# 04_Analog_Part.net
KiCad netlist of a schematic drawn in Altium Designer
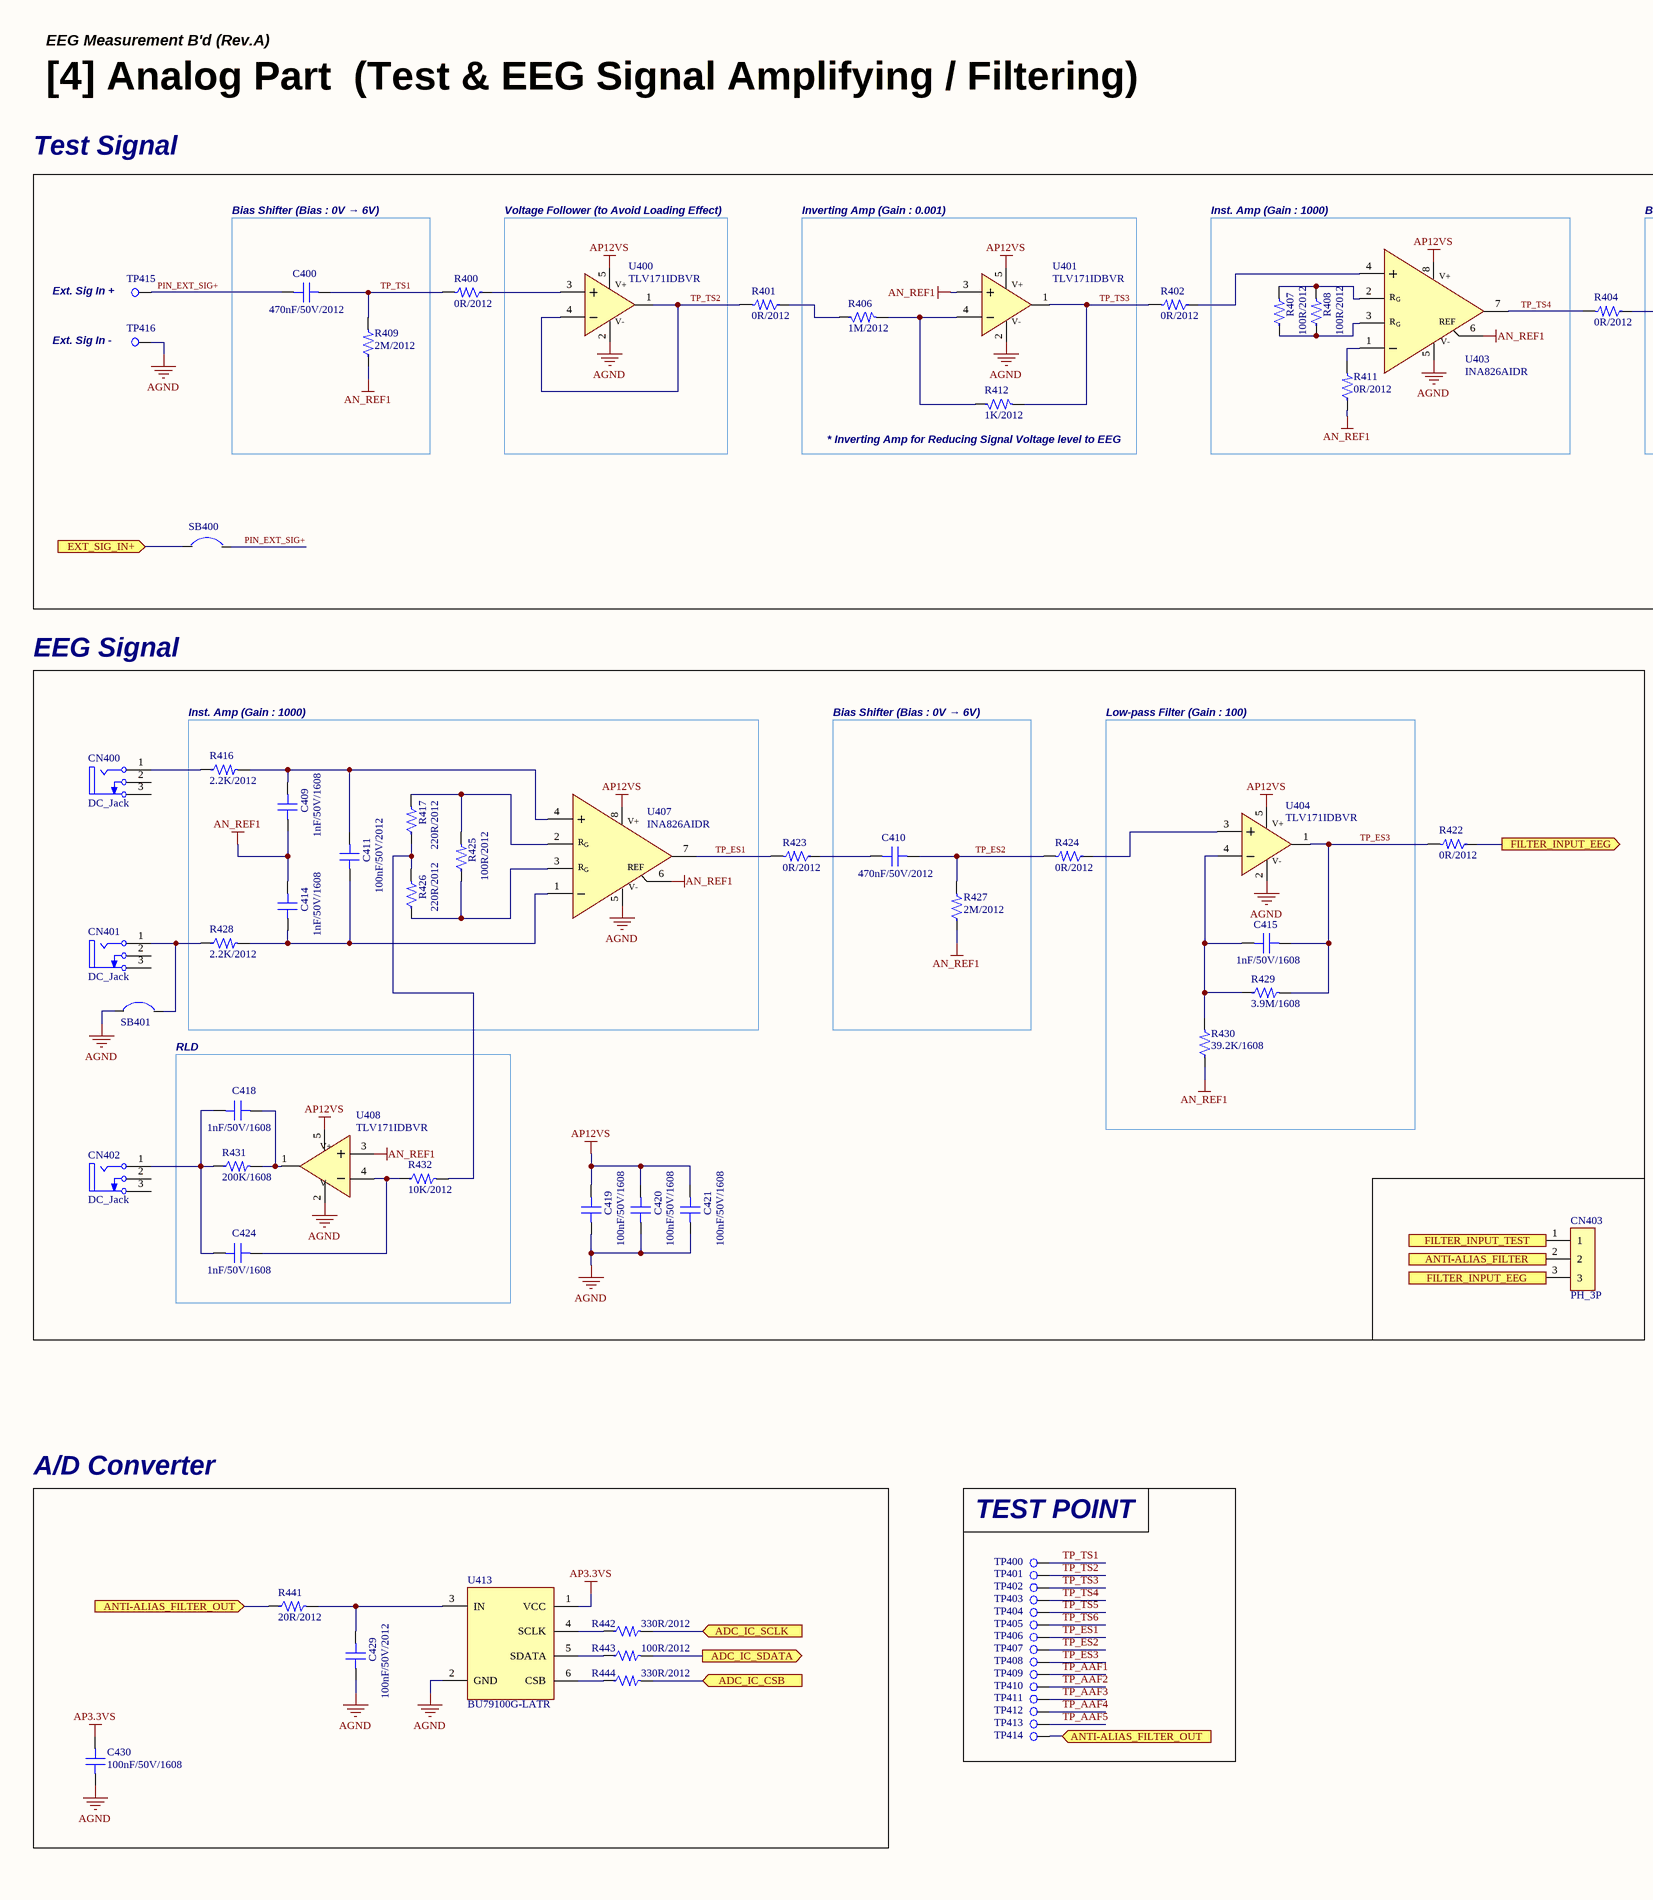
[diagram p0: 04_Analog_Part.SchDoc, left]
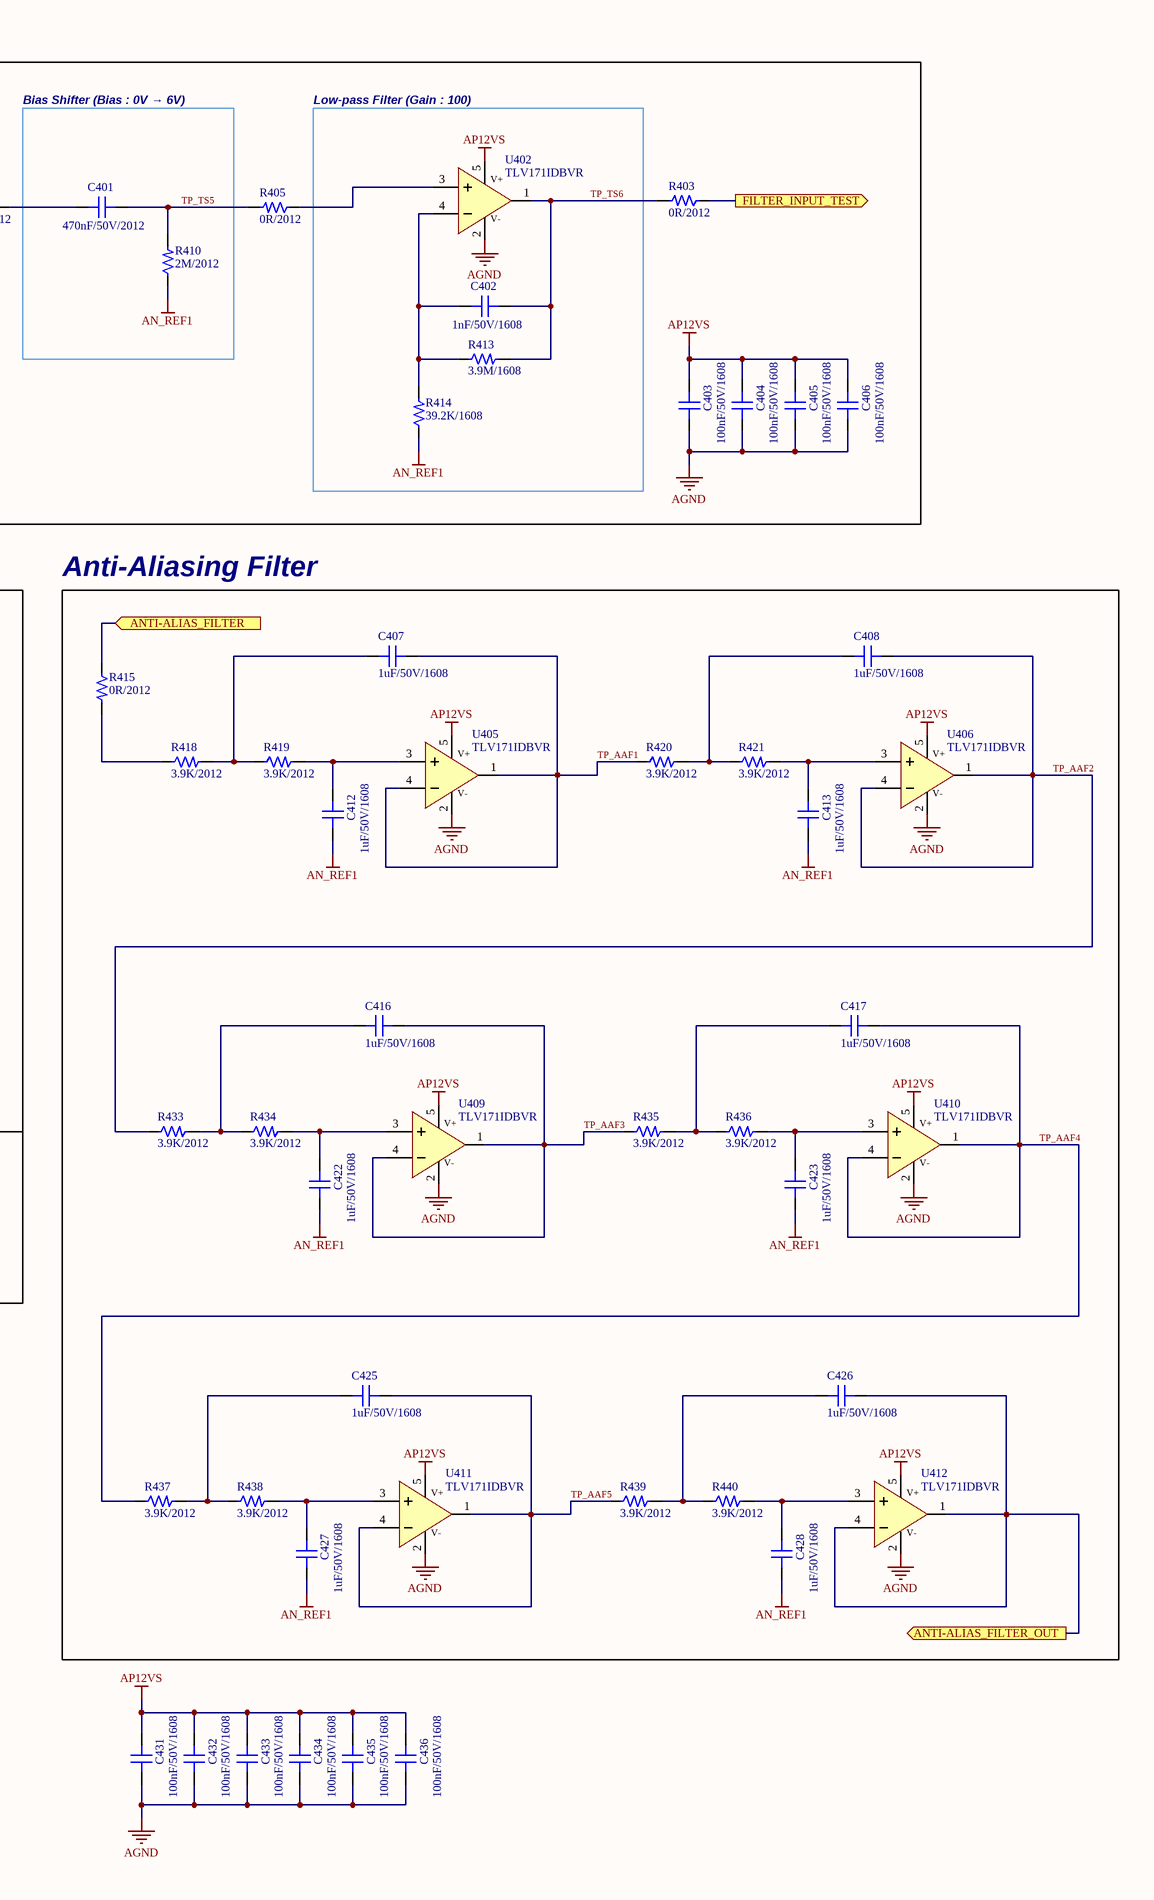
[diagram p1: 04_Analog_Part.SchDoc, right]

(export (version "E")
  (design (tool "Eeschema 10.0.6"))
  (components
    (comp (ref "C400")
      (value "470nF/50V/2012")
      (footprint "CAP 2012 (0805_INCH)")
      (description "Ceramic CAP_470nF/50V/2012")
      (fields (field (name "LCSC PART #") "C13967"))
      (libsource (lib "Arkx") (part "CAP_470nF/50V/2012"))
    )
    (comp (ref "C401")
      (value "470nF/50V/2012")
      (footprint "CAP 2012 (0805_INCH)")
      (description "Ceramic CAP_470nF/50V/2012")
      (fields (field (name "LCSC PART #") "C13967"))
      (libsource (lib "Arkx") (part "CAP_470nF/50V/2012"))
    )
    (comp (ref "C402")
      (value "1nF/50V/1608")
      (footprint "CAP 1608 (0603_INCH)")
      (description "Ceramic CAP_1nF/50V/1608")
      (fields (field (name "LCSC PART #") "C1588"))
      (libsource (lib "Arkx") (part "CAP_1nF/50V/1608"))
    )
    (comp (ref "C403")
      (value "100nF/50V/1608")
      (footprint "CAP 1608 (0603_INCH)")
      (description "Ceramic CAP_100nF/50V/1608")
      (fields (field (name "LCSC PART #") "C14663"))
      (libsource (lib "Arkx") (part "CAP_100nF/50V/1608"))
    )
    (comp (ref "C404")
      (value "100nF/50V/1608")
      (footprint "CAP 1608 (0603_INCH)")
      (description "Ceramic CAP_100nF/50V/1608")
      (fields (field (name "LCSC PART #") "C14663"))
      (libsource (lib "Arkx") (part "CAP_100nF/50V/1608"))
    )
    (comp (ref "C405")
      (value "100nF/50V/1608")
      (footprint "CAP 1608 (0603_INCH)")
      (description "Ceramic CAP_100nF/50V/1608")
      (fields (field (name "LCSC PART #") "C14663"))
      (libsource (lib "Arkx") (part "CAP_100nF/50V/1608"))
    )
    (comp (ref "C406")
      (value "100nF/50V/1608")
      (footprint "CAP 1608 (0603_INCH)")
      (description "Ceramic CAP_100nF/50V/1608")
      (fields (field (name "LCSC PART #") "C14663"))
      (libsource (lib "Arkx") (part "CAP_100nF/50V/1608"))
    )
    (comp (ref "C407")
      (value "1uF/50V/1608")
      (footprint "CAP 1608 (0603_INCH)")
      (description "Ceramic CAP_1uF/50V/1608")
      (fields (field (name "LCSC PART #") "C15849"))
      (libsource (lib "Arkx") (part "CAP_1uF/50V/1608"))
    )
    (comp (ref "C408")
      (value "1uF/50V/1608")
      (footprint "CAP 1608 (0603_INCH)")
      (description "Ceramic CAP_1uF/50V/1608")
      (fields (field (name "LCSC PART #") "C15849"))
      (libsource (lib "Arkx") (part "CAP_1uF/50V/1608"))
    )
    (comp (ref "C409")
      (value "1nF/50V/1608")
      (footprint "CAP 1608 (0603_INCH)")
      (description "Ceramic CAP_1nF/50V/1608")
      (fields (field (name "LCSC PART #") "C1588"))
      (libsource (lib "Arkx") (part "CAP_1nF/50V/1608"))
    )
    (comp (ref "C410")
      (value "470nF/50V/2012")
      (footprint "CAP 2012 (0805_INCH)")
      (description "Ceramic CAP_470nF/50V/2012")
      (fields (field (name "LCSC PART #") "C13967"))
      (libsource (lib "Arkx") (part "CAP_470nF/50V/2012"))
    )
    (comp (ref "C411")
      (value "100nF/50V/2012")
      (footprint "CAP 2012 (0805_INCH)")
      (description "Ceramic CAP_100nF/50V/2012")
      (fields (field (name "LCSC PART #") "C49678"))
      (libsource (lib "Arkx") (part "CAP_100nF/50V/2012"))
    )
    (comp (ref "C412")
      (value "1uF/50V/1608")
      (footprint "CAP 1608 (0603_INCH)")
      (description "Ceramic CAP_1uF/50V/1608")
      (fields (field (name "LCSC PART #") "C15849"))
      (libsource (lib "Arkx") (part "CAP_1uF/50V/1608"))
    )
    (comp (ref "C413")
      (value "1uF/50V/1608")
      (footprint "CAP 1608 (0603_INCH)")
      (description "Ceramic CAP_1uF/50V/1608")
      (fields (field (name "LCSC PART #") "C15849"))
      (libsource (lib "Arkx") (part "CAP_1uF/50V/1608"))
    )
    (comp (ref "C414")
      (value "1nF/50V/1608")
      (footprint "CAP 1608 (0603_INCH)")
      (description "Ceramic CAP_1nF/50V/1608")
      (fields (field (name "LCSC PART #") "C1588"))
      (libsource (lib "Arkx") (part "CAP_1nF/50V/1608"))
    )
    (comp (ref "C415")
      (value "1nF/50V/1608")
      (footprint "CAP 1608 (0603_INCH)")
      (description "Ceramic CAP_1nF/50V/1608")
      (fields (field (name "LCSC PART #") "C1588"))
      (libsource (lib "Arkx") (part "CAP_1nF/50V/1608"))
    )
    (comp (ref "C416")
      (value "1uF/50V/1608")
      (footprint "CAP 1608 (0603_INCH)")
      (description "Ceramic CAP_1uF/50V/1608")
      (fields (field (name "LCSC PART #") "C15849"))
      (libsource (lib "Arkx") (part "CAP_1uF/50V/1608"))
    )
    (comp (ref "C417")
      (value "1uF/50V/1608")
      (footprint "CAP 1608 (0603_INCH)")
      (description "Ceramic CAP_1uF/50V/1608")
      (fields (field (name "LCSC PART #") "C15849"))
      (libsource (lib "Arkx") (part "CAP_1uF/50V/1608"))
    )
    (comp (ref "C418")
      (value "1nF/50V/1608")
      (footprint "CAP 1608 (0603_INCH)")
      (description "Ceramic CAP_1nF/50V/1608")
      (fields (field (name "LCSC PART #") "C1588"))
      (libsource (lib "Arkx") (part "CAP_1nF/50V/1608"))
    )
    (comp (ref "C419")
      (value "100nF/50V/1608")
      (footprint "CAP 1608 (0603_INCH)")
      (description "Ceramic CAP_100nF/50V/1608")
      (fields (field (name "LCSC PART #") "C14663"))
      (libsource (lib "Arkx") (part "CAP_100nF/50V/1608"))
    )
    (comp (ref "C420")
      (value "100nF/50V/1608")
      (footprint "CAP 1608 (0603_INCH)")
      (description "Ceramic CAP_100nF/50V/1608")
      (fields (field (name "LCSC PART #") "C14663"))
      (libsource (lib "Arkx") (part "CAP_100nF/50V/1608"))
    )
    (comp (ref "C421")
      (value "100nF/50V/1608")
      (footprint "CAP 1608 (0603_INCH)")
      (description "Ceramic CAP_100nF/50V/1608")
      (fields (field (name "LCSC PART #") "C14663"))
      (libsource (lib "Arkx") (part "CAP_100nF/50V/1608"))
    )
    (comp (ref "C422")
      (value "1uF/50V/1608")
      (footprint "CAP 1608 (0603_INCH)")
      (description "Ceramic CAP_1uF/50V/1608")
      (fields (field (name "LCSC PART #") "C15849"))
      (libsource (lib "Arkx") (part "CAP_1uF/50V/1608"))
    )
    (comp (ref "C423")
      (value "1uF/50V/1608")
      (footprint "CAP 1608 (0603_INCH)")
      (description "Ceramic CAP_1uF/50V/1608")
      (fields (field (name "LCSC PART #") "C15849"))
      (libsource (lib "Arkx") (part "CAP_1uF/50V/1608"))
    )
    (comp (ref "C424")
      (value "1nF/50V/1608")
      (footprint "CAP 1608 (0603_INCH)")
      (description "Ceramic CAP_1nF/50V/1608")
      (fields (field (name "LCSC PART #") "C1588"))
      (libsource (lib "Arkx") (part "CAP_1nF/50V/1608"))
    )
    (comp (ref "C425")
      (value "1uF/50V/1608")
      (footprint "CAP 1608 (0603_INCH)")
      (description "Ceramic CAP_1uF/50V/1608")
      (fields (field (name "LCSC PART #") "C15849"))
      (libsource (lib "Arkx") (part "CAP_1uF/50V/1608"))
    )
    (comp (ref "C426")
      (value "1uF/50V/1608")
      (footprint "CAP 1608 (0603_INCH)")
      (description "Ceramic CAP_1uF/50V/1608")
      (fields (field (name "LCSC PART #") "C15849"))
      (libsource (lib "Arkx") (part "CAP_1uF/50V/1608"))
    )
    (comp (ref "C427")
      (value "1uF/50V/1608")
      (footprint "CAP 1608 (0603_INCH)")
      (description "Ceramic CAP_1uF/50V/1608")
      (fields (field (name "LCSC PART #") "C15849"))
      (libsource (lib "Arkx") (part "CAP_1uF/50V/1608"))
    )
    (comp (ref "C428")
      (value "1uF/50V/1608")
      (footprint "CAP 1608 (0603_INCH)")
      (description "Ceramic CAP_1uF/50V/1608")
      (fields (field (name "LCSC PART #") "C15849"))
      (libsource (lib "Arkx") (part "CAP_1uF/50V/1608"))
    )
    (comp (ref "C429")
      (value "100nF/50V/2012")
      (footprint "CAP 2012 (0805_INCH)")
      (description "Ceramic CAP_100nF/50V/2012")
      (fields (field (name "LCSC PART #") "C49678"))
      (libsource (lib "Arkx") (part "CAP_100nF/50V/2012"))
    )
    (comp (ref "C430")
      (value "100nF/50V/1608")
      (footprint "CAP 1608 (0603_INCH)")
      (description "Ceramic CAP_100nF/50V/1608")
      (fields (field (name "LCSC PART #") "C14663"))
      (libsource (lib "Arkx") (part "CAP_100nF/50V/1608"))
    )
    (comp (ref "C431")
      (value "100nF/50V/1608")
      (footprint "CAP 1608 (0603_INCH)")
      (description "Ceramic CAP_100nF/50V/1608")
      (fields (field (name "LCSC PART #") "C14663"))
      (libsource (lib "Arkx") (part "CAP_100nF/50V/1608"))
    )
    (comp (ref "C432")
      (value "100nF/50V/1608")
      (footprint "CAP 1608 (0603_INCH)")
      (description "Ceramic CAP_100nF/50V/1608")
      (fields (field (name "LCSC PART #") "C14663"))
      (libsource (lib "Arkx") (part "CAP_100nF/50V/1608"))
    )
    (comp (ref "C433")
      (value "100nF/50V/1608")
      (footprint "CAP 1608 (0603_INCH)")
      (description "Ceramic CAP_100nF/50V/1608")
      (fields (field (name "LCSC PART #") "C14663"))
      (libsource (lib "Arkx") (part "CAP_100nF/50V/1608"))
    )
    (comp (ref "C434")
      (value "100nF/50V/1608")
      (footprint "CAP 1608 (0603_INCH)")
      (description "Ceramic CAP_100nF/50V/1608")
      (fields (field (name "LCSC PART #") "C14663"))
      (libsource (lib "Arkx") (part "CAP_100nF/50V/1608"))
    )
    (comp (ref "C435")
      (value "100nF/50V/1608")
      (footprint "CAP 1608 (0603_INCH)")
      (description "Ceramic CAP_100nF/50V/1608")
      (fields (field (name "LCSC PART #") "C14663"))
      (libsource (lib "Arkx") (part "CAP_100nF/50V/1608"))
    )
    (comp (ref "C436")
      (value "100nF/50V/1608")
      (footprint "CAP 1608 (0603_INCH)")
      (description "Ceramic CAP_100nF/50V/1608")
      (fields (field (name "LCSC PART #") "C14663"))
      (libsource (lib "Arkx") (part "CAP_100nF/50V/1608"))
    )
    (comp (ref "CN400")
      (value "DC_Jack")
      (footprint "CON DC-Jack")
      (libsource (lib "Arkx") (part "CON_DC-Jack"))
    )
    (comp (ref "CN401")
      (value "DC_Jack")
      (footprint "CON DC-Jack")
      (libsource (lib "Arkx") (part "CON_DC-Jack"))
    )
    (comp (ref "CN402")
      (value "DC_Jack")
      (footprint "CON DC-Jack")
      (libsource (lib "Arkx") (part "CON_DC-Jack"))
    )
    (comp (ref "CN403")
      (value "PH_3P")
      (footprint "CON PIN_HEADER-3PIN(2.54MM)")
      (description "CON_PIN_HEADER_SINGLE-3PIN(2.54MM)")
      (libsource (lib "Arkx") (part "CON_PIN_HEADER_SINGLE-3PIN(2.54MM)"))
    )
    (comp (ref "R400")
      (value "0R/2012")
      (footprint "RES 2012 (0805_inch)")
      (description "RES_0R/2012/0.125W")
      (fields (field (name "LCSC PART #") "C17477"))
      (libsource (lib "Arkx") (part "RES_0R/2012/0.125W"))
    )
    (comp (ref "R401")
      (value "0R/2012")
      (footprint "RES 2012 (0805_inch)")
      (description "RES_0R/2012/0.125W")
      (fields (field (name "LCSC PART #") "C17477"))
      (libsource (lib "Arkx") (part "RES_0R/2012/0.125W"))
    )
    (comp (ref "R402")
      (value "0R/2012")
      (footprint "RES 2012 (0805_inch)")
      (description "RES_0R/2012/0.125W")
      (fields (field (name "LCSC PART #") "C17477"))
      (libsource (lib "Arkx") (part "RES_0R/2012/0.125W"))
    )
    (comp (ref "R403")
      (value "0R/2012")
      (footprint "RES 2012 (0805_inch)")
      (description "RES_0R/2012/0.125W")
      (fields (field (name "LCSC PART #") "C17477"))
      (libsource (lib "Arkx") (part "RES_0R/2012/0.125W"))
    )
    (comp (ref "R404")
      (value "0R/2012")
      (footprint "RES 2012 (0805_inch)")
      (description "RES_0R/2012/0.125W")
      (fields (field (name "LCSC PART #") "C17477"))
      (libsource (lib "Arkx") (part "RES_0R/2012/0.125W"))
    )
    (comp (ref "R405")
      (value "0R/2012")
      (footprint "RES 2012 (0805_inch)")
      (description "RES_0R/2012/0.125W")
      (fields (field (name "LCSC PART #") "C17477"))
      (libsource (lib "Arkx") (part "RES_0R/2012/0.125W"))
    )
    (comp (ref "R406")
      (value "1M/2012")
      (footprint "RES 2012 (0805_inch)")
      (description "RES_1M/2012/0.125W")
      (fields (field (name "LCSC PART #") "C17514"))
      (libsource (lib "Arkx") (part "RES_1M/2012/0.125W"))
    )
    (comp (ref "R407")
      (value "100R/2012")
      (footprint "RES 2012 (0805_inch)")
      (description "RES_100R/2012/0.125W")
      (fields (field (name "LCSC PART #") "C17408"))
      (libsource (lib "Arkx") (part "RES_100R/2012/0.125W"))
    )
    (comp (ref "R408")
      (value "100R/2012")
      (footprint "RES 2012 (0805_inch)")
      (description "RES_100R/2012/0.125W")
      (fields (field (name "LCSC PART #") "C17408"))
      (libsource (lib "Arkx") (part "RES_100R/2012/0.125W"))
    )
    (comp (ref "R409")
      (value "2M/2012")
      (footprint "RES 2012 (0805_inch)")
      (description "RES_2M/2012/0.125W")
      (fields (field (name "LCSC PART #") "C26112"))
      (libsource (lib "Arkx") (part "RES_2M/2012/0.125W"))
    )
    (comp (ref "R410")
      (value "2M/2012")
      (footprint "RES 2012 (0805_inch)")
      (description "RES_2M/2012/0.125W")
      (fields (field (name "LCSC PART #") "C26112"))
      (libsource (lib "Arkx") (part "RES_2M/2012/0.125W"))
    )
    (comp (ref "R411")
      (value "0R/2012")
      (footprint "RES 2012 (0805_inch)")
      (description "RES_0R/2012/0.125W")
      (fields (field (name "LCSC PART #") "C17477"))
      (libsource (lib "Arkx") (part "RES_0R/2012/0.125W"))
    )
    (comp (ref "R412")
      (value "1K/2012")
      (footprint "RES 2012 (0805_inch)")
      (description "RES_1K/2012/0.125W")
      (fields (field (name "LCSC PART #") "C17513"))
      (libsource (lib "Arkx") (part "RES_1K/2012/0.125W"))
    )
    (comp (ref "R413")
      (value "3.9M/1608")
      (footprint "RES 1608 (0603_inch)")
      (description "RES_3.9M/1608/0.1W")
      (fields (field (name "LCSC PART #") "C227875"))
      (libsource (lib "Arkx") (part "RES_3.9M/1608/0.1W"))
    )
    (comp (ref "R414")
      (value "39.2K/1608")
      (footprint "RES 1608 (0603_inch)")
      (description "RES_39.2K/1608/0.1W")
      (fields (field (name "LCSC PART #") "C137734"))
      (libsource (lib "Arkx") (part "RES_39.2K/1608/0.1W"))
    )
    (comp (ref "R415")
      (value "0R/2012")
      (footprint "RES 2012 (0805_inch)")
      (description "RES_0R/2012/0.125W")
      (fields (field (name "LCSC PART #") "C17477"))
      (libsource (lib "Arkx") (part "RES_0R/2012/0.125W"))
    )
    (comp (ref "R416")
      (value "2.2K/2012")
      (footprint "RES 2012 (0805_inch)")
      (description "RES_2.2K/2012/0.125W")
      (fields (field (name "LCSC PART #") "C17520"))
      (libsource (lib "Arkx") (part "RES_2.2K/2012/0.125W"))
    )
    (comp (ref "R417")
      (value "220R/2012")
      (footprint "RES 2012 (0805_inch)")
      (description "RES_220R/2012/0.125W")
      (fields (field (name "LCSC PART #") "C17557"))
      (libsource (lib "Arkx") (part "RES_220R/2012/0.125W"))
    )
    (comp (ref "R418")
      (value "3.9K/2012")
      (footprint "RES 2012 (0805_inch)")
      (description "RES_3.9K/2012/0.125W")
      (fields (field (name "LCSC PART #") "C17614"))
      (libsource (lib "Arkx") (part "RES_3.9K/2012/0.125W"))
    )
    (comp (ref "R419")
      (value "3.9K/2012")
      (footprint "RES 2012 (0805_inch)")
      (description "RES_3.9K/2012/0.125W")
      (fields (field (name "LCSC PART #") "C17614"))
      (libsource (lib "Arkx") (part "RES_3.9K/2012/0.125W"))
    )
    (comp (ref "R420")
      (value "3.9K/2012")
      (footprint "RES 2012 (0805_inch)")
      (description "RES_3.9K/2012/0.125W")
      (fields (field (name "LCSC PART #") "C17614"))
      (libsource (lib "Arkx") (part "RES_3.9K/2012/0.125W"))
    )
    (comp (ref "R421")
      (value "3.9K/2012")
      (footprint "RES 2012 (0805_inch)")
      (description "RES_3.9K/2012/0.125W")
      (fields (field (name "LCSC PART #") "C17614"))
      (libsource (lib "Arkx") (part "RES_3.9K/2012/0.125W"))
    )
    (comp (ref "R422")
      (value "0R/2012")
      (footprint "RES 2012 (0805_inch)")
      (description "RES_0R/2012/0.125W")
      (fields (field (name "LCSC PART #") "C17477"))
      (libsource (lib "Arkx") (part "RES_0R/2012/0.125W"))
    )
    (comp (ref "R423")
      (value "0R/2012")
      (footprint "RES 2012 (0805_inch)")
      (description "RES_0R/2012/0.125W")
      (fields (field (name "LCSC PART #") "C17477"))
      (libsource (lib "Arkx") (part "RES_0R/2012/0.125W"))
    )
    (comp (ref "R424")
      (value "0R/2012")
      (footprint "RES 2012 (0805_inch)")
      (description "RES_0R/2012/0.125W")
      (fields (field (name "LCSC PART #") "C17477"))
      (libsource (lib "Arkx") (part "RES_0R/2012/0.125W"))
    )
    (comp (ref "R425")
      (value "100R/2012")
      (footprint "RES 2012 (0805_inch)")
      (description "RES_100R/2012/0.125W")
      (fields (field (name "LCSC PART #") "C17408"))
      (libsource (lib "Arkx") (part "RES_100R/2012/0.125W"))
    )
    (comp (ref "R426")
      (value "220R/2012")
      (footprint "RES 2012 (0805_inch)")
      (description "RES_220R/2012/0.125W")
      (fields (field (name "LCSC PART #") "C17557"))
      (libsource (lib "Arkx") (part "RES_220R/2012/0.125W"))
    )
    (comp (ref "R427")
      (value "2M/2012")
      (footprint "RES 2012 (0805_inch)")
      (description "RES_2M/2012/0.125W")
      (fields (field (name "LCSC PART #") "C26112"))
      (libsource (lib "Arkx") (part "RES_2M/2012/0.125W"))
    )
    (comp (ref "R428")
      (value "2.2K/2012")
      (footprint "RES 2012 (0805_inch)")
      (description "RES_2.2K/2012/0.125W")
      (fields (field (name "LCSC PART #") "C17520"))
      (libsource (lib "Arkx") (part "RES_2.2K/2012/0.125W"))
    )
    (comp (ref "R429")
      (value "3.9M/1608")
      (footprint "RES 1608 (0603_inch)")
      (description "RES_3.9M/1608/0.1W")
      (fields (field (name "LCSC PART #") "C227875"))
      (libsource (lib "Arkx") (part "RES_3.9M/1608/0.1W"))
    )
    (comp (ref "R430")
      (value "39.2K/1608")
      (footprint "RES 1608 (0603_inch)")
      (description "RES_39.2K/1608/0.1W")
      (fields (field (name "LCSC PART #") "C137734"))
      (libsource (lib "Arkx") (part "RES_39.2K/1608/0.1W"))
    )
    (comp (ref "R431")
      (value "200K/1608")
      (footprint "RES 1608 (0603_inch)")
      (description "RES_200K/1608/0.1W")
      (fields (field (name "LCSC PART #") "C25811"))
      (libsource (lib "Arkx") (part "RES_200K/1608/0.1W"))
    )
    (comp (ref "R432")
      (value "10K/2012")
      (footprint "RES 2012 (0805_inch)")
      (description "RES_10K/2012/0.125W")
      (fields (field (name "LCSC PART #") "C17414"))
      (libsource (lib "Arkx") (part "RES_10K/2012/0.125W"))
    )
    (comp (ref "R433")
      (value "3.9K/2012")
      (footprint "RES 2012 (0805_inch)")
      (description "RES_3.9K/2012/0.125W")
      (fields (field (name "LCSC PART #") "C17614"))
      (libsource (lib "Arkx") (part "RES_3.9K/2012/0.125W"))
    )
    (comp (ref "R434")
      (value "3.9K/2012")
      (footprint "RES 2012 (0805_inch)")
      (description "RES_3.9K/2012/0.125W")
      (fields (field (name "LCSC PART #") "C17614"))
      (libsource (lib "Arkx") (part "RES_3.9K/2012/0.125W"))
    )
    (comp (ref "R435")
      (value "3.9K/2012")
      (footprint "RES 2012 (0805_inch)")
      (description "RES_3.9K/2012/0.125W")
      (fields (field (name "LCSC PART #") "C17614"))
      (libsource (lib "Arkx") (part "RES_3.9K/2012/0.125W"))
    )
    (comp (ref "R436")
      (value "3.9K/2012")
      (footprint "RES 2012 (0805_inch)")
      (description "RES_3.9K/2012/0.125W")
      (fields (field (name "LCSC PART #") "C17614"))
      (libsource (lib "Arkx") (part "RES_3.9K/2012/0.125W"))
    )
    (comp (ref "R437")
      (value "3.9K/2012")
      (footprint "RES 2012 (0805_inch)")
      (description "RES_3.9K/2012/0.125W")
      (fields (field (name "LCSC PART #") "C17614"))
      (libsource (lib "Arkx") (part "RES_3.9K/2012/0.125W"))
    )
    (comp (ref "R438")
      (value "3.9K/2012")
      (footprint "RES 2012 (0805_inch)")
      (description "RES_3.9K/2012/0.125W")
      (fields (field (name "LCSC PART #") "C17614"))
      (libsource (lib "Arkx") (part "RES_3.9K/2012/0.125W"))
    )
    (comp (ref "R439")
      (value "3.9K/2012")
      (footprint "RES 2012 (0805_inch)")
      (description "RES_3.9K/2012/0.125W")
      (fields (field (name "LCSC PART #") "C17614"))
      (libsource (lib "Arkx") (part "RES_3.9K/2012/0.125W"))
    )
    (comp (ref "R440")
      (value "3.9K/2012")
      (footprint "RES 2012 (0805_inch)")
      (description "RES_3.9K/2012/0.125W")
      (fields (field (name "LCSC PART #") "C17614"))
      (libsource (lib "Arkx") (part "RES_3.9K/2012/0.125W"))
    )
    (comp (ref "R441")
      (value "20R/2012")
      (footprint "RES 2012 (0805_inch)")
      (description "RES_20R/2012/0.125W")
      (fields (field (name "LCSC PART #") "C17544"))
      (libsource (lib "Arkx") (part "RES_20R/2012/0.125W"))
    )
    (comp (ref "R442")
      (value "330R/2012")
      (footprint "RES 2012 (0805_inch)")
      (description "RES_330R/2012/0.125W")
      (fields (field (name "LCSC PART #") "C17630"))
      (libsource (lib "Arkx") (part "RES_330R/2012/0.125W"))
    )
    (comp (ref "R443")
      (value "100R/2012")
      (footprint "RES 2012 (0805_inch)")
      (description "RES_100R/2012/0.125W")
      (fields (field (name "LCSC PART #") "C17408"))
      (libsource (lib "Arkx") (part "RES_100R/2012/0.125W"))
    )
    (comp (ref "R444")
      (value "330R/2012")
      (footprint "RES 2012 (0805_inch)")
      (description "RES_330R/2012/0.125W")
      (fields (field (name "LCSC PART #") "C17630"))
      (libsource (lib "Arkx") (part "RES_330R/2012/0.125W"))
    )
    (comp (ref "SB400")
      (value "SB")
      (footprint "SB (Solder-Bridge)")
      (description "SB_Solder-Bridge")
      (libsource (lib "Arkx") (part "SB_Solder-Bridge"))
    )
    (comp (ref "SB401")
      (value "SB")
      (footprint "SB (Solder-Bridge)")
      (description "SB_Solder-Bridge")
      (libsource (lib "Arkx") (part "SB_Solder-Bridge"))
    )
    (comp (ref "TP400")
      (value "TP_HOLE(1MM)")
      (footprint "TP_HOLE(1MM)")
      (libsource (lib "Arkx") (part "TP_HOLE(1MM)"))
    )
    (comp (ref "TP401")
      (value "TP_HOLE(1MM)")
      (footprint "TP_HOLE(1MM)")
      (libsource (lib "Arkx") (part "TP_HOLE(1MM)"))
    )
    (comp (ref "TP402")
      (value "TP_HOLE(1MM)")
      (footprint "TP_HOLE(1MM)")
      (libsource (lib "Arkx") (part "TP_HOLE(1MM)"))
    )
    (comp (ref "TP403")
      (value "TP_HOLE(1MM)")
      (footprint "TP_HOLE(1MM)")
      (libsource (lib "Arkx") (part "TP_HOLE(1MM)"))
    )
    (comp (ref "TP404")
      (value "TP_HOLE(1MM)")
      (footprint "TP_HOLE(1MM)")
      (libsource (lib "Arkx") (part "TP_HOLE(1MM)"))
    )
    (comp (ref "TP405")
      (value "TP_HOLE(1MM)")
      (footprint "TP_HOLE(1MM)")
      (libsource (lib "Arkx") (part "TP_HOLE(1MM)"))
    )
    (comp (ref "TP406")
      (value "TP_HOLE(1MM)")
      (footprint "TP_HOLE(1MM)")
      (libsource (lib "Arkx") (part "TP_HOLE(1MM)"))
    )
    (comp (ref "TP407")
      (value "TP_HOLE(1MM)")
      (footprint "TP_HOLE(1MM)")
      (libsource (lib "Arkx") (part "TP_HOLE(1MM)"))
    )
    (comp (ref "TP408")
      (value "TP_HOLE(1MM)")
      (footprint "TP_HOLE(1MM)")
      (libsource (lib "Arkx") (part "TP_HOLE(1MM)"))
    )
    (comp (ref "TP409")
      (value "TP_HOLE(1MM)")
      (footprint "TP_HOLE(1MM)")
      (libsource (lib "Arkx") (part "TP_HOLE(1MM)"))
    )
    (comp (ref "TP410")
      (value "TP_HOLE(1MM)")
      (footprint "TP_HOLE(1MM)")
      (libsource (lib "Arkx") (part "TP_HOLE(1MM)"))
    )
    (comp (ref "TP411")
      (value "TP_HOLE(1MM)")
      (footprint "TP_HOLE(1MM)")
      (libsource (lib "Arkx") (part "TP_HOLE(1MM)"))
    )
    (comp (ref "TP412")
      (value "TP_HOLE(1MM)")
      (footprint "TP_HOLE(1MM)")
      (libsource (lib "Arkx") (part "TP_HOLE(1MM)"))
    )
    (comp (ref "TP413")
      (value "TP_HOLE(1MM)")
      (footprint "TP_HOLE(1MM)")
      (libsource (lib "Arkx") (part "TP_HOLE(1MM)"))
    )
    (comp (ref "TP414")
      (value "TP_HOLE(1MM)")
      (footprint "TP_HOLE(1MM)")
      (libsource (lib "Arkx") (part "TP_HOLE(1MM)"))
    )
    (comp (ref "TP415")
      (value "TP_HOLE(1MM)")
      (footprint "TP_HOLE(1MM)")
      (libsource (lib "Arkx") (part "TP_HOLE(1MM)"))
    )
    (comp (ref "TP416")
      (value "TP_HOLE(1MM)")
      (footprint "TP_HOLE(1MM)")
      (libsource (lib "Arkx") (part "TP_HOLE(1MM)"))
    )
    (comp (ref "U400")
      (value "TLV171IDBVR")
      (footprint "SOT-23-5 (TI DBV PACKAGE)")
      (description "Single, 36-V, 3-MHz, low-power operational amplifier for cost-sensitive applications")
      (fields (field (name "LCSC PART #") "C2864299"))
      (libsource (lib "Arkx") (part "IC_OPAMP_TLV171IDBVR"))
    )
    (comp (ref "U401")
      (value "TLV171IDBVR")
      (footprint "SOT-23-5 (TI DBV PACKAGE)")
      (description "Single, 36-V, 3-MHz, low-power operational amplifier for cost-sensitive applications")
      (fields (field (name "LCSC PART #") "C2864299"))
      (libsource (lib "Arkx") (part "IC_OPAMP_TLV171IDBVR"))
    )
    (comp (ref "U402")
      (value "TLV171IDBVR")
      (footprint "SOT-23-5 (TI DBV PACKAGE)")
      (description "Single, 36-V, 3-MHz, low-power operational amplifier for cost-sensitive applications")
      (fields (field (name "LCSC PART #") "C2864299"))
      (libsource (lib "Arkx") (part "IC_OPAMP_TLV171IDBVR"))
    )
    (comp (ref "U403")
      (value "INA826AIDR")
      (footprint "IC_SOIC-8 (4.90x3.90mm)")
      (description "35nA 40uV 1MHz Single SOIC-8  Instrumentation OpAmps ROHS")
      (fields (field (name "LCSC PART #") "C38433"))
      (libsource (lib "Arkx") (part "IC_INST-AMP_INA826AIDR"))
    )
    (comp (ref "U404")
      (value "TLV171IDBVR")
      (footprint "SOT-23-5 (TI DBV PACKAGE)")
      (description "Single, 36-V, 3-MHz, low-power operational amplifier for cost-sensitive applications")
      (fields (field (name "LCSC PART #") "C2864299"))
      (libsource (lib "Arkx") (part "IC_OPAMP_TLV171IDBVR"))
    )
    (comp (ref "U405")
      (value "TLV171IDBVR")
      (footprint "SOT-23-5 (TI DBV PACKAGE)")
      (description "Single, 36-V, 3-MHz, low-power operational amplifier for cost-sensitive applications")
      (fields (field (name "LCSC PART #") "C2864299"))
      (libsource (lib "Arkx") (part "IC_OPAMP_TLV171IDBVR"))
    )
    (comp (ref "U406")
      (value "TLV171IDBVR")
      (footprint "SOT-23-5 (TI DBV PACKAGE)")
      (description "Single, 36-V, 3-MHz, low-power operational amplifier for cost-sensitive applications")
      (fields (field (name "LCSC PART #") "C2864299"))
      (libsource (lib "Arkx") (part "IC_OPAMP_TLV171IDBVR"))
    )
    (comp (ref "U407")
      (value "INA826AIDR")
      (footprint "IC_SOIC-8 (4.90x3.90mm)")
      (description "35nA 40uV 1MHz Single SOIC-8  Instrumentation OpAmps ROHS")
      (fields (field (name "LCSC PART #") "C38433"))
      (libsource (lib "Arkx") (part "IC_INST-AMP_INA826AIDR"))
    )
    (comp (ref "U408")
      (value "TLV171IDBVR")
      (footprint "SOT-23-5 (TI DBV PACKAGE)")
      (description "Single, 36-V, 3-MHz, low-power operational amplifier for cost-sensitive applications")
      (fields (field (name "LCSC PART #") "C2864299"))
      (libsource (lib "Arkx") (part "IC_OPAMP_TLV171IDBVR"))
    )
    (comp (ref "U409")
      (value "TLV171IDBVR")
      (footprint "SOT-23-5 (TI DBV PACKAGE)")
      (description "Single, 36-V, 3-MHz, low-power operational amplifier for cost-sensitive applications")
      (fields (field (name "LCSC PART #") "C2864299"))
      (libsource (lib "Arkx") (part "IC_OPAMP_TLV171IDBVR"))
    )
    (comp (ref "U410")
      (value "TLV171IDBVR")
      (footprint "SOT-23-5 (TI DBV PACKAGE)")
      (description "Single, 36-V, 3-MHz, low-power operational amplifier for cost-sensitive applications")
      (fields (field (name "LCSC PART #") "C2864299"))
      (libsource (lib "Arkx") (part "IC_OPAMP_TLV171IDBVR"))
    )
    (comp (ref "U411")
      (value "TLV171IDBVR")
      (footprint "SOT-23-5 (TI DBV PACKAGE)")
      (description "Single, 36-V, 3-MHz, low-power operational amplifier for cost-sensitive applications")
      (fields (field (name "LCSC PART #") "C2864299"))
      (libsource (lib "Arkx") (part "IC_OPAMP_TLV171IDBVR"))
    )
    (comp (ref "U412")
      (value "TLV171IDBVR")
      (footprint "SOT-23-5 (TI DBV PACKAGE)")
      (description "Single, 36-V, 3-MHz, low-power operational amplifier for cost-sensitive applications")
      (fields (field (name "LCSC PART #") "C2864299"))
      (libsource (lib "Arkx") (part "IC_OPAMP_TLV171IDBVR"))
    )
    (comp (ref "U413")
      (value "BU79100G-LATR")
      (footprint "IC_SOT-23-6")
      (fields (field (name "LCSC PART #") "None"))
      (libsource (lib "Arkx") (part "IC_ADC_BU79100G-LATR"))
    )
  )
  (nets
    (net (code "1") (name "/ADC_IC_CSB") (class "Default")
      (node (ref "R444") (pin "2") (pinfunction "2_2") (pintype "passive"))
    )
    (net (code "2") (name "/ADC_IC_SCLK") (class "Default")
      (node (ref "R442") (pin "2") (pinfunction "2_2") (pintype "passive"))
    )
    (net (code "3") (name "/ADC_IC_SDATA") (class "Default")
      (node (ref "R443") (pin "2") (pinfunction "2_2") (pintype "passive"))
    )
    (net (code "4") (name "/ANTI-ALIAS_FILTER") (class "Default")
      (node (ref "CN403") (pin "2") (pinfunction "2_2") (pintype "passive"))
      (node (ref "R415") (pin "1") (pinfunction "1_1") (pintype "passive"))
    )
    (net (code "5") (name "/ANTI-ALIAS_FILTER_OUT") (class "Default")
      (node (ref "C426") (pin "2") (pinfunction "2_2") (pintype "passive"))
      (node (ref "R441") (pin "1") (pinfunction "1_1") (pintype "passive"))
      (node (ref "TP414") (pin "1") (pinfunction "TP_1") (pintype "passive"))
      (node (ref "U412") (pin "1") (pinfunction "OUT_1") (pintype "passive"))
      (node (ref "U412") (pin "4") (pinfunction "IN-_4") (pintype "passive"))
    )
    (net (code "6") (name "/EXT_SIG_IN+") (class "Default")
      (node (ref "SB400") (pin "1") (pinfunction "1_1") (pintype "passive"))
    )
    (net (code "7") (name "/FILTER_INPUT_EEG") (class "Default")
      (node (ref "CN403") (pin "3") (pinfunction "3_3") (pintype "passive"))
      (node (ref "R422") (pin "1") (pinfunction "1_1") (pintype "passive"))
    )
    (net (code "8") (name "/FILTER_INPUT_TEST") (class "Default")
      (node (ref "CN403") (pin "1") (pinfunction "1_1") (pintype "passive"))
      (node (ref "R403") (pin "1") (pinfunction "1_1") (pintype "passive"))
    )
    (net (code "9") (name "/PIN_EXT_SIG+") (class "Default")
      (node (ref "C400") (pin "1") (pinfunction "1_1") (pintype "passive"))
      (node (ref "SB400") (pin "2") (pinfunction "2_2") (pintype "passive"))
      (node (ref "TP415") (pin "1") (pinfunction "TP_1") (pintype "passive"))
    )
    (net (code "10") (name "/TP_AAF1") (class "Default")
      (node (ref "C407") (pin "2") (pinfunction "2_2") (pintype "passive"))
      (node (ref "R420") (pin "1") (pinfunction "1_1") (pintype "passive"))
      (node (ref "TP409") (pin "1") (pinfunction "TP_1") (pintype "passive"))
      (node (ref "U405") (pin "1") (pinfunction "OUT_1") (pintype "passive"))
      (node (ref "U405") (pin "4") (pinfunction "IN-_4") (pintype "passive"))
    )
    (net (code "11") (name "/TP_AAF2") (class "Default")
      (node (ref "C408") (pin "2") (pinfunction "2_2") (pintype "passive"))
      (node (ref "R433") (pin "1") (pinfunction "1_1") (pintype "passive"))
      (node (ref "TP410") (pin "1") (pinfunction "TP_1") (pintype "passive"))
      (node (ref "U406") (pin "1") (pinfunction "OUT_1") (pintype "passive"))
      (node (ref "U406") (pin "4") (pinfunction "IN-_4") (pintype "passive"))
    )
    (net (code "12") (name "/TP_AAF3") (class "Default")
      (node (ref "C416") (pin "2") (pinfunction "2_2") (pintype "passive"))
      (node (ref "R435") (pin "1") (pinfunction "1_1") (pintype "passive"))
      (node (ref "TP411") (pin "1") (pinfunction "TP_1") (pintype "passive"))
      (node (ref "U409") (pin "1") (pinfunction "OUT_1") (pintype "passive"))
      (node (ref "U409") (pin "4") (pinfunction "IN-_4") (pintype "passive"))
    )
    (net (code "13") (name "/TP_AAF4") (class "Default")
      (node (ref "C417") (pin "2") (pinfunction "2_2") (pintype "passive"))
      (node (ref "R437") (pin "1") (pinfunction "1_1") (pintype "passive"))
      (node (ref "TP412") (pin "1") (pinfunction "TP_1") (pintype "passive"))
      (node (ref "U410") (pin "1") (pinfunction "OUT_1") (pintype "passive"))
      (node (ref "U410") (pin "4") (pinfunction "IN-_4") (pintype "passive"))
    )
    (net (code "14") (name "/TP_AAF5") (class "Default")
      (node (ref "C425") (pin "2") (pinfunction "2_2") (pintype "passive"))
      (node (ref "R439") (pin "1") (pinfunction "1_1") (pintype "passive"))
      (node (ref "TP413") (pin "1") (pinfunction "TP_1") (pintype "passive"))
      (node (ref "U411") (pin "1") (pinfunction "OUT_1") (pintype "passive"))
      (node (ref "U411") (pin "4") (pinfunction "IN-_4") (pintype "passive"))
    )
    (net (code "15") (name "/TP_ES1") (class "Default")
      (node (ref "R423") (pin "2") (pinfunction "2_2") (pintype "passive"))
      (node (ref "TP406") (pin "1") (pinfunction "TP_1") (pintype "passive"))
      (node (ref "U407") (pin "7") (pinfunction "VOUT_7") (pintype "passive"))
    )
    (net (code "16") (name "/TP_ES2") (class "Default")
      (node (ref "C410") (pin "2") (pinfunction "2_2") (pintype "passive"))
      (node (ref "R424") (pin "2") (pinfunction "2_2") (pintype "passive"))
      (node (ref "R427") (pin "2") (pinfunction "2_2") (pintype "passive"))
      (node (ref "TP407") (pin "1") (pinfunction "TP_1") (pintype "passive"))
    )
    (net (code "17") (name "/TP_ES3") (class "Default")
      (node (ref "C415") (pin "1") (pinfunction "1_1") (pintype "passive"))
      (node (ref "R422") (pin "2") (pinfunction "2_2") (pintype "passive"))
      (node (ref "R429") (pin "2") (pinfunction "2_2") (pintype "passive"))
      (node (ref "TP408") (pin "1") (pinfunction "TP_1") (pintype "passive"))
      (node (ref "U404") (pin "1") (pinfunction "OUT_1") (pintype "passive"))
    )
    (net (code "18") (name "/TP_TS1") (class "Default")
      (node (ref "C400") (pin "2") (pinfunction "2_2") (pintype "passive"))
      (node (ref "R400") (pin "2") (pinfunction "2_2") (pintype "passive"))
      (node (ref "R409") (pin "2") (pinfunction "2_2") (pintype "passive"))
      (node (ref "TP400") (pin "1") (pinfunction "TP_1") (pintype "passive"))
    )
    (net (code "19") (name "/TP_TS2") (class "Default")
      (node (ref "R401") (pin "2") (pinfunction "2_2") (pintype "passive"))
      (node (ref "TP401") (pin "1") (pinfunction "TP_1") (pintype "passive"))
      (node (ref "U400") (pin "1") (pinfunction "OUT_1") (pintype "passive"))
      (node (ref "U400") (pin "4") (pinfunction "IN-_4") (pintype "passive"))
    )
    (net (code "20") (name "/TP_TS3") (class "Default")
      (node (ref "R402") (pin "2") (pinfunction "2_2") (pintype "passive"))
      (node (ref "R412") (pin "2") (pinfunction "2_2") (pintype "passive"))
      (node (ref "TP402") (pin "1") (pinfunction "TP_1") (pintype "passive"))
      (node (ref "U401") (pin "1") (pinfunction "OUT_1") (pintype "passive"))
    )
    (net (code "21") (name "/TP_TS4") (class "Default")
      (node (ref "R404") (pin "2") (pinfunction "2_2") (pintype "passive"))
      (node (ref "TP403") (pin "1") (pinfunction "TP_1") (pintype "passive"))
      (node (ref "U403") (pin "7") (pinfunction "VOUT_7") (pintype "passive"))
    )
    (net (code "22") (name "/TP_TS5") (class "Default")
      (node (ref "C401") (pin "2") (pinfunction "2_2") (pintype "passive"))
      (node (ref "R405") (pin "2") (pinfunction "2_2") (pintype "passive"))
      (node (ref "R410") (pin "2") (pinfunction "2_2") (pintype "passive"))
      (node (ref "TP404") (pin "1") (pinfunction "TP_1") (pintype "passive"))
    )
    (net (code "23") (name "/TP_TS6") (class "Default")
      (node (ref "C402") (pin "1") (pinfunction "1_1") (pintype "passive"))
      (node (ref "R403") (pin "2") (pinfunction "2_2") (pintype "passive"))
      (node (ref "R413") (pin "2") (pinfunction "2_2") (pintype "passive"))
      (node (ref "TP405") (pin "1") (pinfunction "TP_1") (pintype "passive"))
      (node (ref "U402") (pin "1") (pinfunction "OUT_1") (pintype "passive"))
    )
    (net (code "24") (name "AGND") (class "Default")
      (node (ref "C403") (pin "1") (pinfunction "1_1") (pintype "passive"))
      (node (ref "C404") (pin "1") (pinfunction "1_1") (pintype "passive"))
      (node (ref "C405") (pin "1") (pinfunction "1_1") (pintype "passive"))
      (node (ref "C406") (pin "1") (pinfunction "1_1") (pintype "passive"))
      (node (ref "C419") (pin "1") (pinfunction "1_1") (pintype "passive"))
      (node (ref "C420") (pin "1") (pinfunction "1_1") (pintype "passive"))
      (node (ref "C421") (pin "1") (pinfunction "1_1") (pintype "passive"))
      (node (ref "C429") (pin "1") (pinfunction "1_1") (pintype "passive"))
      (node (ref "C430") (pin "1") (pinfunction "1_1") (pintype "passive"))
      (node (ref "C431") (pin "1") (pinfunction "1_1") (pintype "passive"))
      (node (ref "C432") (pin "1") (pinfunction "1_1") (pintype "passive"))
      (node (ref "C433") (pin "1") (pinfunction "1_1") (pintype "passive"))
      (node (ref "C434") (pin "1") (pinfunction "1_1") (pintype "passive"))
      (node (ref "C435") (pin "1") (pinfunction "1_1") (pintype "passive"))
      (node (ref "C436") (pin "1") (pinfunction "1_1") (pintype "passive"))
      (node (ref "SB401") (pin "1") (pinfunction "1_1") (pintype "passive"))
      (node (ref "TP416") (pin "1") (pinfunction "TP_1") (pintype "passive"))
      (node (ref "U400") (pin "2") (pinfunction "V-_2") (pintype "passive"))
      (node (ref "U401") (pin "2") (pinfunction "V-_2") (pintype "passive"))
      (node (ref "U402") (pin "2") (pinfunction "V-_2") (pintype "passive"))
      (node (ref "U403") (pin "5") (pinfunction "V-_5") (pintype "passive"))
      (node (ref "U404") (pin "2") (pinfunction "V-_2") (pintype "passive"))
      (node (ref "U405") (pin "2") (pinfunction "V-_2") (pintype "passive"))
      (node (ref "U406") (pin "2") (pinfunction "V-_2") (pintype "passive"))
      (node (ref "U407") (pin "5") (pinfunction "V-_5") (pintype "passive"))
      (node (ref "U408") (pin "2") (pinfunction "V-_2") (pintype "passive"))
      (node (ref "U409") (pin "2") (pinfunction "V-_2") (pintype "passive"))
      (node (ref "U410") (pin "2") (pinfunction "V-_2") (pintype "passive"))
      (node (ref "U411") (pin "2") (pinfunction "V-_2") (pintype "passive"))
      (node (ref "U412") (pin "2") (pinfunction "V-_2") (pintype "passive"))
      (node (ref "U413") (pin "2") (pinfunction "GND_2") (pintype "passive"))
    )
    (net (code "25") (name "AN_REF1") (class "Default")
      (node (ref "C409") (pin "1") (pinfunction "1_1") (pintype "passive"))
      (node (ref "C412") (pin "1") (pinfunction "1_1") (pintype "passive"))
      (node (ref "C413") (pin "1") (pinfunction "1_1") (pintype "passive"))
      (node (ref "C414") (pin "2") (pinfunction "2_2") (pintype "passive"))
      (node (ref "C422") (pin "1") (pinfunction "1_1") (pintype "passive"))
      (node (ref "C423") (pin "1") (pinfunction "1_1") (pintype "passive"))
      (node (ref "C427") (pin "1") (pinfunction "1_1") (pintype "passive"))
      (node (ref "C428") (pin "1") (pinfunction "1_1") (pintype "passive"))
      (node (ref "R409") (pin "1") (pinfunction "1_1") (pintype "passive"))
      (node (ref "R410") (pin "1") (pinfunction "1_1") (pintype "passive"))
      (node (ref "R411") (pin "1") (pinfunction "1_1") (pintype "passive"))
      (node (ref "R414") (pin "1") (pinfunction "1_1") (pintype "passive"))
      (node (ref "R427") (pin "1") (pinfunction "1_1") (pintype "passive"))
      (node (ref "R430") (pin "1") (pinfunction "1_1") (pintype "passive"))
      (node (ref "U401") (pin "3") (pinfunction "IN+_3") (pintype "passive"))
      (node (ref "U403") (pin "6") (pinfunction "REF_6") (pintype "passive"))
      (node (ref "U407") (pin "6") (pinfunction "REF_6") (pintype "passive"))
      (node (ref "U408") (pin "3") (pinfunction "IN+_3") (pintype "passive"))
    )
    (net (code "26") (name "AP3.3VS") (class "Default")
      (node (ref "C430") (pin "2") (pinfunction "2_2") (pintype "passive"))
      (node (ref "U413") (pin "1") (pinfunction "VCC_1") (pintype "passive"))
    )
    (net (code "27") (name "AP12VS") (class "Default")
      (node (ref "C403") (pin "2") (pinfunction "2_2") (pintype "passive"))
      (node (ref "C404") (pin "2") (pinfunction "2_2") (pintype "passive"))
      (node (ref "C405") (pin "2") (pinfunction "2_2") (pintype "passive"))
      (node (ref "C406") (pin "2") (pinfunction "2_2") (pintype "passive"))
      (node (ref "C419") (pin "2") (pinfunction "2_2") (pintype "passive"))
      (node (ref "C420") (pin "2") (pinfunction "2_2") (pintype "passive"))
      (node (ref "C421") (pin "2") (pinfunction "2_2") (pintype "passive"))
      (node (ref "C431") (pin "2") (pinfunction "2_2") (pintype "passive"))
      (node (ref "C432") (pin "2") (pinfunction "2_2") (pintype "passive"))
      (node (ref "C433") (pin "2") (pinfunction "2_2") (pintype "passive"))
      (node (ref "C434") (pin "2") (pinfunction "2_2") (pintype "passive"))
      (node (ref "C435") (pin "2") (pinfunction "2_2") (pintype "passive"))
      (node (ref "C436") (pin "2") (pinfunction "2_2") (pintype "passive"))
      (node (ref "U400") (pin "5") (pinfunction "V+_5") (pintype "passive"))
      (node (ref "U401") (pin "5") (pinfunction "V+_5") (pintype "passive"))
      (node (ref "U402") (pin "5") (pinfunction "V+_5") (pintype "passive"))
      (node (ref "U403") (pin "8") (pinfunction "V+_8") (pintype "passive"))
      (node (ref "U404") (pin "5") (pinfunction "V+_5") (pintype "passive"))
      (node (ref "U405") (pin "5") (pinfunction "V+_5") (pintype "passive"))
      (node (ref "U406") (pin "5") (pinfunction "V+_5") (pintype "passive"))
      (node (ref "U407") (pin "8") (pinfunction "V+_8") (pintype "passive"))
      (node (ref "U408") (pin "5") (pinfunction "V+_5") (pintype "passive"))
      (node (ref "U409") (pin "5") (pinfunction "V+_5") (pintype "passive"))
      (node (ref "U410") (pin "5") (pinfunction "V+_5") (pintype "passive"))
      (node (ref "U411") (pin "5") (pinfunction "V+_5") (pintype "passive"))
      (node (ref "U412") (pin "5") (pinfunction "V+_5") (pintype "passive"))
    )
    (net (code "28") (name "Net-(C401-Pad1)") (class "Default")
      (node (ref "C401") (pin "1") (pinfunction "1_1") (pintype "passive"))
      (node (ref "R404") (pin "1") (pinfunction "1_1") (pintype "passive"))
    )
    (net (code "29") (name "Net-(C407-Pad1)") (class "Default")
      (node (ref "C407") (pin "1") (pinfunction "1_1") (pintype "passive"))
      (node (ref "R418") (pin "2") (pinfunction "2_2") (pintype "passive"))
      (node (ref "R419") (pin "1") (pinfunction "1_1") (pintype "passive"))
    )
    (net (code "30") (name "Net-(C408-Pad1)") (class "Default")
      (node (ref "C408") (pin "1") (pinfunction "1_1") (pintype "passive"))
      (node (ref "R420") (pin "2") (pinfunction "2_2") (pintype "passive"))
      (node (ref "R421") (pin "1") (pinfunction "1_1") (pintype "passive"))
    )
    (net (code "31") (name "Net-(C410-Pad1)") (class "Default")
      (node (ref "C410") (pin "1") (pinfunction "1_1") (pintype "passive"))
      (node (ref "R423") (pin "1") (pinfunction "1_1") (pintype "passive"))
    )
    (net (code "32") (name "Net-(C416-Pad1)") (class "Default")
      (node (ref "C416") (pin "1") (pinfunction "1_1") (pintype "passive"))
      (node (ref "R433") (pin "2") (pinfunction "2_2") (pintype "passive"))
      (node (ref "R434") (pin "1") (pinfunction "1_1") (pintype "passive"))
    )
    (net (code "33") (name "Net-(C417-Pad1)") (class "Default")
      (node (ref "C417") (pin "1") (pinfunction "1_1") (pintype "passive"))
      (node (ref "R435") (pin "2") (pinfunction "2_2") (pintype "passive"))
      (node (ref "R436") (pin "1") (pinfunction "1_1") (pintype "passive"))
    )
    (net (code "34") (name "Net-(C425-Pad1)") (class "Default")
      (node (ref "C425") (pin "1") (pinfunction "1_1") (pintype "passive"))
      (node (ref "R437") (pin "2") (pinfunction "2_2") (pintype "passive"))
      (node (ref "R438") (pin "1") (pinfunction "1_1") (pintype "passive"))
    )
    (net (code "35") (name "Net-(C426-Pad1)") (class "Default")
      (node (ref "C426") (pin "1") (pinfunction "1_1") (pintype "passive"))
      (node (ref "R439") (pin "2") (pinfunction "2_2") (pintype "passive"))
      (node (ref "R440") (pin "1") (pinfunction "1_1") (pintype "passive"))
    )
    (net (code "36") (name "Net-(CN400-VCC)") (class "Default")
      (node (ref "CN400") (pin "1") (pinfunction "VCC_1") (pintype "power_in"))
      (node (ref "R416") (pin "1") (pinfunction "1_1") (pintype "passive"))
    )
    (net (code "37") (name "Net-(CN401-VCC)") (class "Default")
      (node (ref "CN401") (pin "1") (pinfunction "VCC_1") (pintype "power_in"))
      (node (ref "R428") (pin "1") (pinfunction "1_1") (pintype "passive"))
      (node (ref "SB401") (pin "2") (pinfunction "2_2") (pintype "passive"))
    )
    (net (code "38") (name "Net-(CN402-VCC)") (class "Default")
      (node (ref "C418") (pin "2") (pinfunction "2_2") (pintype "passive"))
      (node (ref "C424") (pin "2") (pinfunction "2_2") (pintype "passive"))
      (node (ref "CN402") (pin "1") (pinfunction "VCC_1") (pintype "power_in"))
      (node (ref "R431") (pin "1") (pinfunction "1_1") (pintype "passive"))
    )
    (net (code "39") (name "Net-(R401-Pad1)") (class "Default")
      (node (ref "R401") (pin "1") (pinfunction "1_1") (pintype "passive"))
      (node (ref "R406") (pin "1") (pinfunction "1_1") (pintype "passive"))
    )
    (net (code "40") (name "Net-(R415-Pad2)") (class "Default")
      (node (ref "R415") (pin "2") (pinfunction "2_2") (pintype "passive"))
      (node (ref "R418") (pin "1") (pinfunction "1_1") (pintype "passive"))
    )
    (net (code "41") (name "Net-(R417-Pad1)") (class "Default")
      (node (ref "R417") (pin "1") (pinfunction "1_1") (pintype "passive"))
      (node (ref "R426") (pin "2") (pinfunction "2_2") (pintype "passive"))
      (node (ref "R432") (pin "2") (pinfunction "2_2") (pintype "passive"))
    )
    (net (code "42") (name "Net-(U400-IN+)") (class "Default")
      (node (ref "R400") (pin "1") (pinfunction "1_1") (pintype "passive"))
      (node (ref "U400") (pin "3") (pinfunction "IN+_3") (pintype "passive"))
    )
    (net (code "43") (name "Net-(U401-IN-)") (class "Default")
      (node (ref "R406") (pin "2") (pinfunction "2_2") (pintype "passive"))
      (node (ref "R412") (pin "1") (pinfunction "1_1") (pintype "passive"))
      (node (ref "U401") (pin "4") (pinfunction "IN-_4") (pintype "passive"))
    )
    (net (code "44") (name "Net-(U402-IN+)") (class "Default")
      (node (ref "R405") (pin "1") (pinfunction "1_1") (pintype "passive"))
      (node (ref "U402") (pin "3") (pinfunction "IN+_3") (pintype "passive"))
    )
    (net (code "45") (name "Net-(U402-IN-)") (class "Default")
      (node (ref "C402") (pin "2") (pinfunction "2_2") (pintype "passive"))
      (node (ref "R413") (pin "1") (pinfunction "1_1") (pintype "passive"))
      (node (ref "R414") (pin "2") (pinfunction "2_2") (pintype "passive"))
      (node (ref "U402") (pin "4") (pinfunction "IN-_4") (pintype "passive"))
    )
    (net (code "46") (name "Net-(U403-IN+)") (class "Default")
      (node (ref "R402") (pin "1") (pinfunction "1_1") (pintype "passive"))
      (node (ref "U403") (pin "4") (pinfunction "IN+_4") (pintype "passive"))
    )
    (net (code "47") (name "Net-(U403-IN-)") (class "Default")
      (node (ref "R411") (pin "2") (pinfunction "2_2") (pintype "passive"))
      (node (ref "U403") (pin "1") (pinfunction "IN-_1") (pintype "passive"))
    )
    (net (code "48") (name "Net-(U403-RG+)") (class "Default")
      (node (ref "R407") (pin "2") (pinfunction "2_2") (pintype "passive"))
      (node (ref "R408") (pin "2") (pinfunction "2_2") (pintype "passive"))
      (node (ref "U403") (pin "2") (pinfunction "RG+_2") (pintype "passive"))
    )
    (net (code "49") (name "Net-(U403-RG-)") (class "Default")
      (node (ref "R407") (pin "1") (pinfunction "1_1") (pintype "passive"))
      (node (ref "R408") (pin "1") (pinfunction "1_1") (pintype "passive"))
      (node (ref "U403") (pin "3") (pinfunction "RG-_3") (pintype "passive"))
    )
    (net (code "50") (name "Net-(U404-IN+)") (class "Default")
      (node (ref "R424") (pin "1") (pinfunction "1_1") (pintype "passive"))
      (node (ref "U404") (pin "3") (pinfunction "IN+_3") (pintype "passive"))
    )
    (net (code "51") (name "Net-(U404-IN-)") (class "Default")
      (node (ref "C415") (pin "2") (pinfunction "2_2") (pintype "passive"))
      (node (ref "R429") (pin "1") (pinfunction "1_1") (pintype "passive"))
      (node (ref "R430") (pin "2") (pinfunction "2_2") (pintype "passive"))
      (node (ref "U404") (pin "4") (pinfunction "IN-_4") (pintype "passive"))
    )
    (net (code "52") (name "Net-(U405-IN+)") (class "Default")
      (node (ref "C412") (pin "2") (pinfunction "2_2") (pintype "passive"))
      (node (ref "R419") (pin "2") (pinfunction "2_2") (pintype "passive"))
      (node (ref "U405") (pin "3") (pinfunction "IN+_3") (pintype "passive"))
    )
    (net (code "53") (name "Net-(U406-IN+)") (class "Default")
      (node (ref "C413") (pin "2") (pinfunction "2_2") (pintype "passive"))
      (node (ref "R421") (pin "2") (pinfunction "2_2") (pintype "passive"))
      (node (ref "U406") (pin "3") (pinfunction "IN+_3") (pintype "passive"))
    )
    (net (code "54") (name "Net-(U407-IN+)") (class "Default")
      (node (ref "C409") (pin "2") (pinfunction "2_2") (pintype "passive"))
      (node (ref "C411") (pin "2") (pinfunction "2_2") (pintype "passive"))
      (node (ref "R416") (pin "2") (pinfunction "2_2") (pintype "passive"))
      (node (ref "U407") (pin "4") (pinfunction "IN+_4") (pintype "passive"))
    )
    (net (code "55") (name "Net-(U407-IN-)") (class "Default")
      (node (ref "C411") (pin "1") (pinfunction "1_1") (pintype "passive"))
      (node (ref "C414") (pin "1") (pinfunction "1_1") (pintype "passive"))
      (node (ref "R428") (pin "2") (pinfunction "2_2") (pintype "passive"))
      (node (ref "U407") (pin "1") (pinfunction "IN-_1") (pintype "passive"))
    )
    (net (code "56") (name "Net-(U407-RG+)") (class "Default")
      (node (ref "R417") (pin "2") (pinfunction "2_2") (pintype "passive"))
      (node (ref "R425") (pin "2") (pinfunction "2_2") (pintype "passive"))
      (node (ref "U407") (pin "2") (pinfunction "RG+_2") (pintype "passive"))
    )
    (net (code "57") (name "Net-(U407-RG-)") (class "Default")
      (node (ref "R425") (pin "1") (pinfunction "1_1") (pintype "passive"))
      (node (ref "R426") (pin "1") (pinfunction "1_1") (pintype "passive"))
      (node (ref "U407") (pin "3") (pinfunction "RG-_3") (pintype "passive"))
    )
    (net (code "58") (name "Net-(U408-IN-)") (class "Default")
      (node (ref "C424") (pin "1") (pinfunction "1_1") (pintype "passive"))
      (node (ref "R432") (pin "1") (pinfunction "1_1") (pintype "passive"))
      (node (ref "U408") (pin "4") (pinfunction "IN-_4") (pintype "passive"))
    )
    (net (code "59") (name "Net-(U408-OUT)") (class "Default")
      (node (ref "C418") (pin "1") (pinfunction "1_1") (pintype "passive"))
      (node (ref "R431") (pin "2") (pinfunction "2_2") (pintype "passive"))
      (node (ref "U408") (pin "1") (pinfunction "OUT_1") (pintype "passive"))
    )
    (net (code "60") (name "Net-(U409-IN+)") (class "Default")
      (node (ref "C422") (pin "2") (pinfunction "2_2") (pintype "passive"))
      (node (ref "R434") (pin "2") (pinfunction "2_2") (pintype "passive"))
      (node (ref "U409") (pin "3") (pinfunction "IN+_3") (pintype "passive"))
    )
    (net (code "61") (name "Net-(U410-IN+)") (class "Default")
      (node (ref "C423") (pin "2") (pinfunction "2_2") (pintype "passive"))
      (node (ref "R436") (pin "2") (pinfunction "2_2") (pintype "passive"))
      (node (ref "U410") (pin "3") (pinfunction "IN+_3") (pintype "passive"))
    )
    (net (code "62") (name "Net-(U411-IN+)") (class "Default")
      (node (ref "C427") (pin "2") (pinfunction "2_2") (pintype "passive"))
      (node (ref "R438") (pin "2") (pinfunction "2_2") (pintype "passive"))
      (node (ref "U411") (pin "3") (pinfunction "IN+_3") (pintype "passive"))
    )
    (net (code "63") (name "Net-(U412-IN+)") (class "Default")
      (node (ref "C428") (pin "2") (pinfunction "2_2") (pintype "passive"))
      (node (ref "R440") (pin "2") (pinfunction "2_2") (pintype "passive"))
      (node (ref "U412") (pin "3") (pinfunction "IN+_3") (pintype "passive"))
    )
    (net (code "64") (name "Net-(U413-CSB)") (class "Default")
      (node (ref "R444") (pin "1") (pinfunction "1_1") (pintype "passive"))
      (node (ref "U413") (pin "6") (pinfunction "CSB_6") (pintype "passive"))
    )
    (net (code "65") (name "Net-(U413-IN)") (class "Default")
      (node (ref "C429") (pin "2") (pinfunction "2_2") (pintype "passive"))
      (node (ref "R441") (pin "2") (pinfunction "2_2") (pintype "passive"))
      (node (ref "U413") (pin "3") (pinfunction "IN_3") (pintype "passive"))
    )
    (net (code "66") (name "Net-(U413-SCLK)") (class "Default")
      (node (ref "R442") (pin "1") (pinfunction "1_1") (pintype "passive"))
      (node (ref "U413") (pin "4") (pinfunction "SCLK_4") (pintype "passive"))
    )
    (net (code "67") (name "Net-(U413-SDATA)") (class "Default")
      (node (ref "R443") (pin "1") (pinfunction "1_1") (pintype "passive"))
      (node (ref "U413") (pin "5") (pinfunction "SDATA_5") (pintype "passive"))
    )
    (net (code "68") (name "unconnected-(CN400-GND-Pad2)") (class "Default")
      (node (ref "CN400") (pin "2") (pinfunction "GND_2") (pintype "power_in"))
    )
    (net (code "69") (name "unconnected-(CN400-GND-Pad3)") (class "Default")
      (node (ref "CN400") (pin "3") (pinfunction "GND_3") (pintype "power_in"))
    )
    (net (code "70") (name "unconnected-(CN401-GND-Pad2)") (class "Default")
      (node (ref "CN401") (pin "2") (pinfunction "GND_2") (pintype "power_in"))
    )
    (net (code "71") (name "unconnected-(CN401-GND-Pad3)") (class "Default")
      (node (ref "CN401") (pin "3") (pinfunction "GND_3") (pintype "power_in"))
    )
    (net (code "72") (name "unconnected-(CN402-GND-Pad2)") (class "Default")
      (node (ref "CN402") (pin "2") (pinfunction "GND_2") (pintype "power_in"))
    )
    (net (code "73") (name "unconnected-(CN402-GND-Pad3)") (class "Default")
      (node (ref "CN402") (pin "3") (pinfunction "GND_3") (pintype "power_in"))
    )
  )
)
